# ProPrj__PCB__2025-12-27.net
KiCad netlist of a schematic drawn in EasyEDA Pro
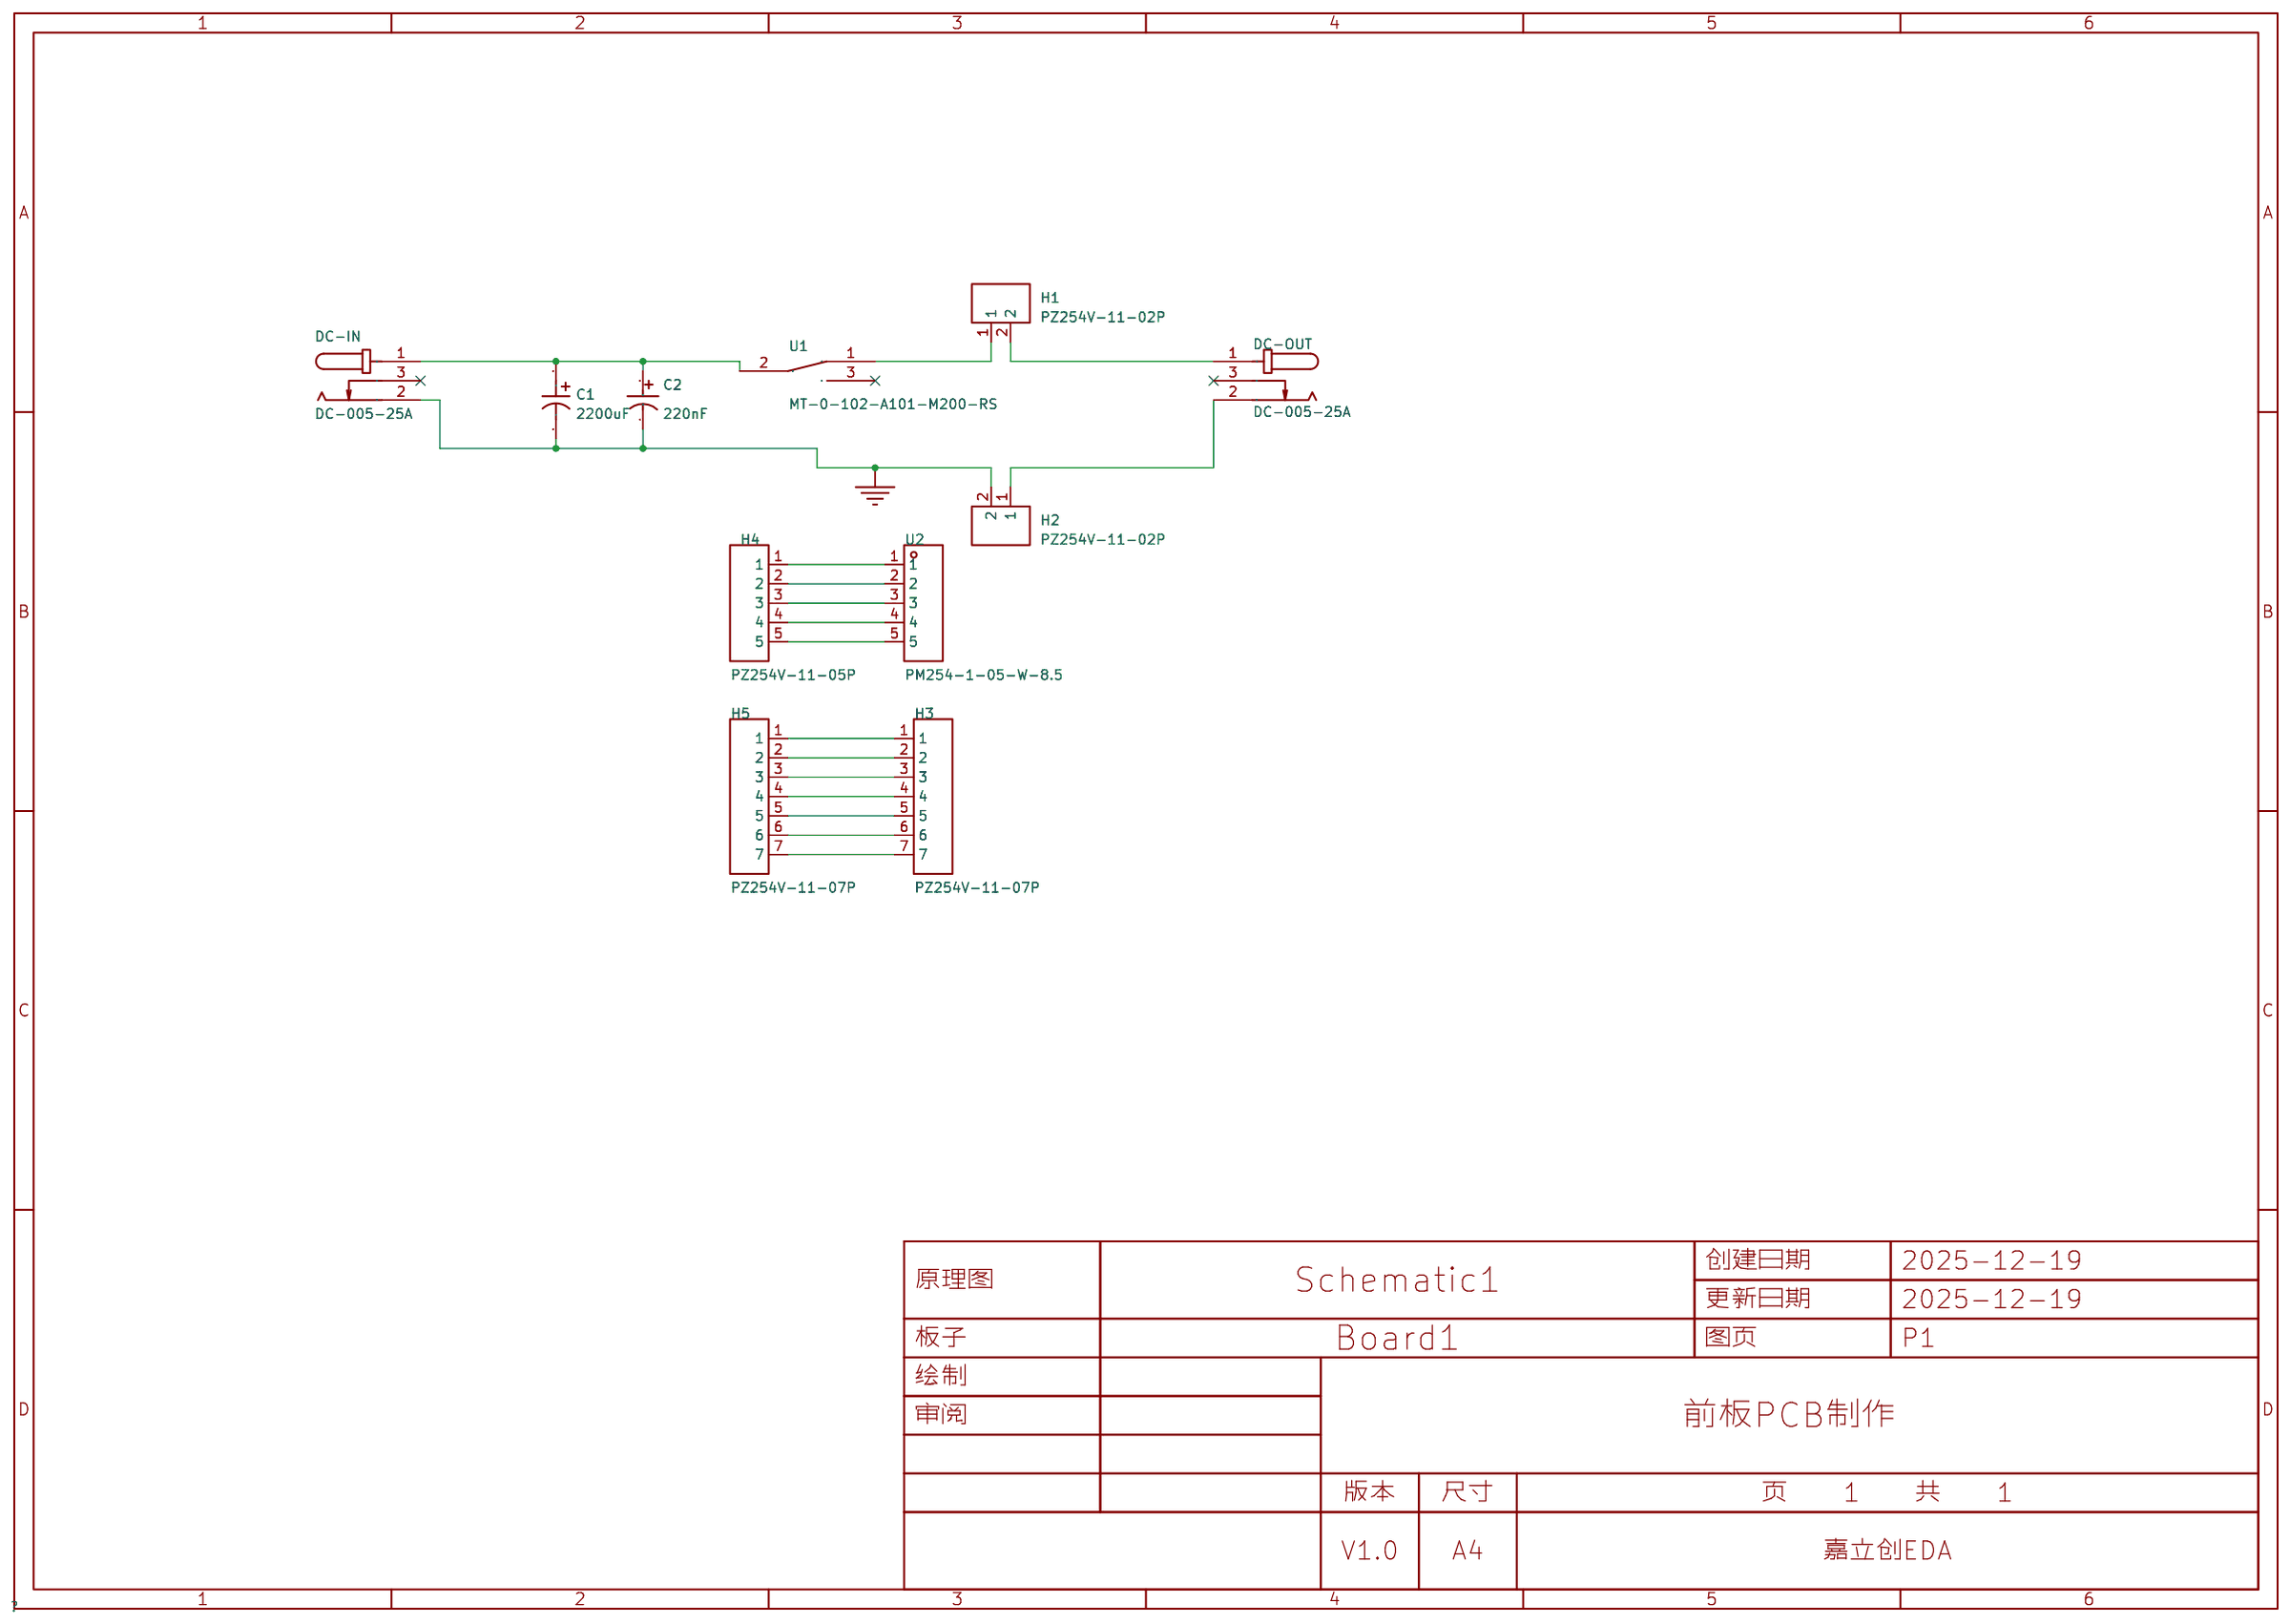
[diagram p0: schematic sheet]

(export (version "E")
  (design (tool "Eeschema 10.0.6"))
  (components
    (comp (ref "C1")
      (value "2200uF")
      (footprint "easyedapro:CAP-TH_BD13.0-P5.00-D0.6-FD")
      (fields
        (field (name "Manufacturer Part") "ERA25V2200M13X21")
        (field (name "Manufacturer") "JIERR(捷而瑞)")
      )
      (libsource (lib "easyedapro") (part "ERA25V2200M13X21"))
    )
    (comp (ref "C2")
      (value "220nF")
      (footprint "easyedapro:CAP-TH_BD5.0-P2.00-D0.8-FD")
      (fields
        (field (name "Manufacturer Part") "KM224M050D11RR0VH2FP0")
        (field (name "Manufacturer") "Chengx(承兴)")
      )
      (libsource (lib "easyedapro") (part "0.22uF 50V 5*11"))
    )
    (comp (ref "DC-IN")
      (value "DC-005-25A")
      (footprint "easyedapro:DC-IN-TH_DC005")
      (description "连接器类型:DC电源插座;安装方式:弯插;触点内径:2.5mm;触点外径:6.4mm;额定电流:500mA;额定电压:30V;工作温度:-25℃~+80℃;")
      (fields (field (name "Manufacturer") "韩国韩荣"))
      (libsource (lib "easyedapro") (part "DC-005-25A"))
    )
    (comp (ref "DC-OUT")
      (value "DC-005-25A")
      (footprint "easyedapro:DC-IN-TH_DC005")
      (description "连接器类型:DC电源插座;安装方式:弯插;触点内径:2.5mm;触点外径:6.4mm;额定电流:500mA;额定电压:30V;工作温度:-25℃~+80℃;")
      (fields (field (name "Manufacturer") "韩国韩荣"))
      (libsource (lib "easyedapro") (part "DC-005-25A"))
    )
    (comp (ref "H1")
      (value "PZ254V-11-02P")
      (footprint "easyedapro:HDR-TH_2P-P2.54-V-M")
      (fields (field (name "Manufacturer") "XFCN(兴飞)"))
      (libsource (lib "easyedapro") (part "PZ254V-11-02P"))
    )
    (comp (ref "H2")
      (value "PZ254V-11-02P")
      (footprint "easyedapro:HDR-TH_2P-P2.54-V-M")
      (fields (field (name "Manufacturer") "XFCN(兴飞)"))
      (libsource (lib "easyedapro") (part "PZ254V-11-02P"))
    )
    (comp (ref "H3")
      (value "PZ254V-11-07P")
      (footprint "easyedapro:HDR-TH_7P-P2.54-V-M")
      (fields (field (name "Manufacturer") "XFCN(兴飞)"))
      (libsource (lib "easyedapro") (part "PZ254V-11-07P"))
    )
    (comp (ref "H4")
      (value "PZ254V-11-05P")
      (footprint "easyedapro:HDR-TH_5P-P2.54-V-M")
      (fields (field (name "Manufacturer") "XFCN(兴飞)"))
      (libsource (lib "easyedapro") (part "PZ254V-11-05P"))
    )
    (comp (ref "H5")
      (value "PZ254V-11-07P")
      (footprint "easyedapro:HDR-TH_7P-P2.54-V-M")
      (fields (field (name "Manufacturer") "XFCN(兴飞)"))
      (libsource (lib "easyedapro") (part "PZ254V-11-07P"))
    )
    (comp (ref "U1")
      (value "MT-0-102-A101-M200-RS")
      (footprint "easyedapro:SW-TH_MT-0-103-A101-M200-RS")
      (fields (field (name "Manufacturer") "YUEN FUNG(源丰)"))
      (libsource (lib "easyedapro") (part "MT-0-102-A101-M200-RS+PJ"))
    )
    (comp (ref "U2")
      (value "PM254-1-05-W-8.5")
      (footprint "easyedapro:HDR-TH_5P-P2.54-H-F-W10.0-N")
      (fields (field (name "Manufacturer") "HCTL(华灿天禄)"))
      (libsource (lib "easyedapro") (part "PM254-1-05-W-8.5"))
    )
  )
  (nets
    (net (code "1") (name "GND") (class "Default")
      (node (ref "C1") (pin "2") (pinfunction "2_2") (pintype "input"))
      (node (ref "C2") (pin "2") (pinfunction "2_2") (pintype "input"))
      (node (ref "DC-IN") (pin "2") (pinfunction "2_2") (pintype "unspecified"))
      (node (ref "H2") (pin "2") (pinfunction "2_2") (pintype "unspecified"))
    )
    (net (code "2") (name "Net-(C1-Pad1)") (class "Default")
      (node (ref "C1") (pin "1") (pinfunction "1_1") (pintype "input"))
      (node (ref "C2") (pin "1") (pinfunction "1_1") (pintype "input"))
      (node (ref "DC-IN") (pin "1") (pinfunction "1_1") (pintype "unspecified"))
      (node (ref "U1") (pin "2") (pinfunction "2_2") (pintype "unspecified"))
    )
    (net (code "3") (name "Net-(DC-OUT-Pad1)") (class "Default")
      (node (ref "DC-OUT") (pin "1") (pinfunction "1_1") (pintype "unspecified"))
      (node (ref "H1") (pin "2") (pinfunction "2_2") (pintype "unspecified"))
    )
    (net (code "4") (name "Net-(DC-OUT-Pad2)") (class "Default")
      (node (ref "DC-OUT") (pin "2") (pinfunction "2_2") (pintype "unspecified"))
      (node (ref "H2") (pin "1") (pinfunction "1_1") (pintype "unspecified"))
    )
    (net (code "5") (name "Net-(H1-Pad1)") (class "Default")
      (node (ref "H1") (pin "1") (pinfunction "1_1") (pintype "unspecified"))
      (node (ref "U1") (pin "1") (pinfunction "1_1") (pintype "unspecified"))
    )
    (net (code "6") (name "Net-(H3-Pad1)") (class "Default")
      (node (ref "H3") (pin "1") (pinfunction "1_1") (pintype "unspecified"))
      (node (ref "H5") (pin "1") (pinfunction "1_1") (pintype "unspecified"))
    )
    (net (code "7") (name "Net-(H3-Pad2)") (class "Default")
      (node (ref "H3") (pin "2") (pinfunction "2_2") (pintype "unspecified"))
      (node (ref "H5") (pin "2") (pinfunction "2_2") (pintype "unspecified"))
    )
    (net (code "8") (name "Net-(H3-Pad3)") (class "Default")
      (node (ref "H3") (pin "3") (pinfunction "3_3") (pintype "unspecified"))
      (node (ref "H5") (pin "3") (pinfunction "3_3") (pintype "unspecified"))
    )
    (net (code "9") (name "Net-(H3-Pad4)") (class "Default")
      (node (ref "H3") (pin "4") (pinfunction "4_4") (pintype "unspecified"))
      (node (ref "H5") (pin "4") (pinfunction "4_4") (pintype "unspecified"))
    )
    (net (code "10") (name "Net-(H3-Pad5)") (class "Default")
      (node (ref "H3") (pin "5") (pinfunction "5_5") (pintype "unspecified"))
      (node (ref "H5") (pin "5") (pinfunction "5_5") (pintype "unspecified"))
    )
    (net (code "11") (name "Net-(H3-Pad6)") (class "Default")
      (node (ref "H3") (pin "6") (pinfunction "6_6") (pintype "unspecified"))
      (node (ref "H5") (pin "6") (pinfunction "6_6") (pintype "unspecified"))
    )
    (net (code "12") (name "Net-(H3-Pad7)") (class "Default")
      (node (ref "H3") (pin "7") (pinfunction "7_7") (pintype "unspecified"))
      (node (ref "H5") (pin "7") (pinfunction "7_7") (pintype "unspecified"))
    )
    (net (code "13") (name "Net-(H4-Pad1)") (class "Default")
      (node (ref "H4") (pin "1") (pinfunction "1_1") (pintype "unspecified"))
      (node (ref "U2") (pin "1") (pinfunction "1_1") (pintype "unspecified"))
    )
    (net (code "14") (name "Net-(H4-Pad2)") (class "Default")
      (node (ref "H4") (pin "2") (pinfunction "2_2") (pintype "unspecified"))
      (node (ref "U2") (pin "2") (pinfunction "2_2") (pintype "unspecified"))
    )
    (net (code "15") (name "Net-(H4-Pad3)") (class "Default")
      (node (ref "H4") (pin "3") (pinfunction "3_3") (pintype "unspecified"))
      (node (ref "U2") (pin "3") (pinfunction "3_3") (pintype "unspecified"))
    )
    (net (code "16") (name "Net-(H4-Pad4)") (class "Default")
      (node (ref "H4") (pin "4") (pinfunction "4_4") (pintype "unspecified"))
      (node (ref "U2") (pin "4") (pinfunction "4_4") (pintype "unspecified"))
    )
    (net (code "17") (name "Net-(H4-Pad5)") (class "Default")
      (node (ref "H4") (pin "5") (pinfunction "5_5") (pintype "unspecified"))
      (node (ref "U2") (pin "5") (pinfunction "5_5") (pintype "unspecified"))
    )
    (net (code "18") (name "unconnected-(DC-IN-Pad3)") (class "Default")
      (node (ref "DC-IN") (pin "3") (pinfunction "3_3") (pintype "unspecified+no_connect"))
    )
    (net (code "19") (name "unconnected-(DC-OUT-Pad3)") (class "Default")
      (node (ref "DC-OUT") (pin "3") (pinfunction "3_3") (pintype "unspecified+no_connect"))
    )
    (net (code "20") (name "unconnected-(U1-Pad3)") (class "Default")
      (node (ref "U1") (pin "3") (pinfunction "3_3") (pintype "unspecified+no_connect"))
    )
  )
)
